# AuxilliaryLEDs.net
KiCad netlist of a schematic drawn in Altium Designer
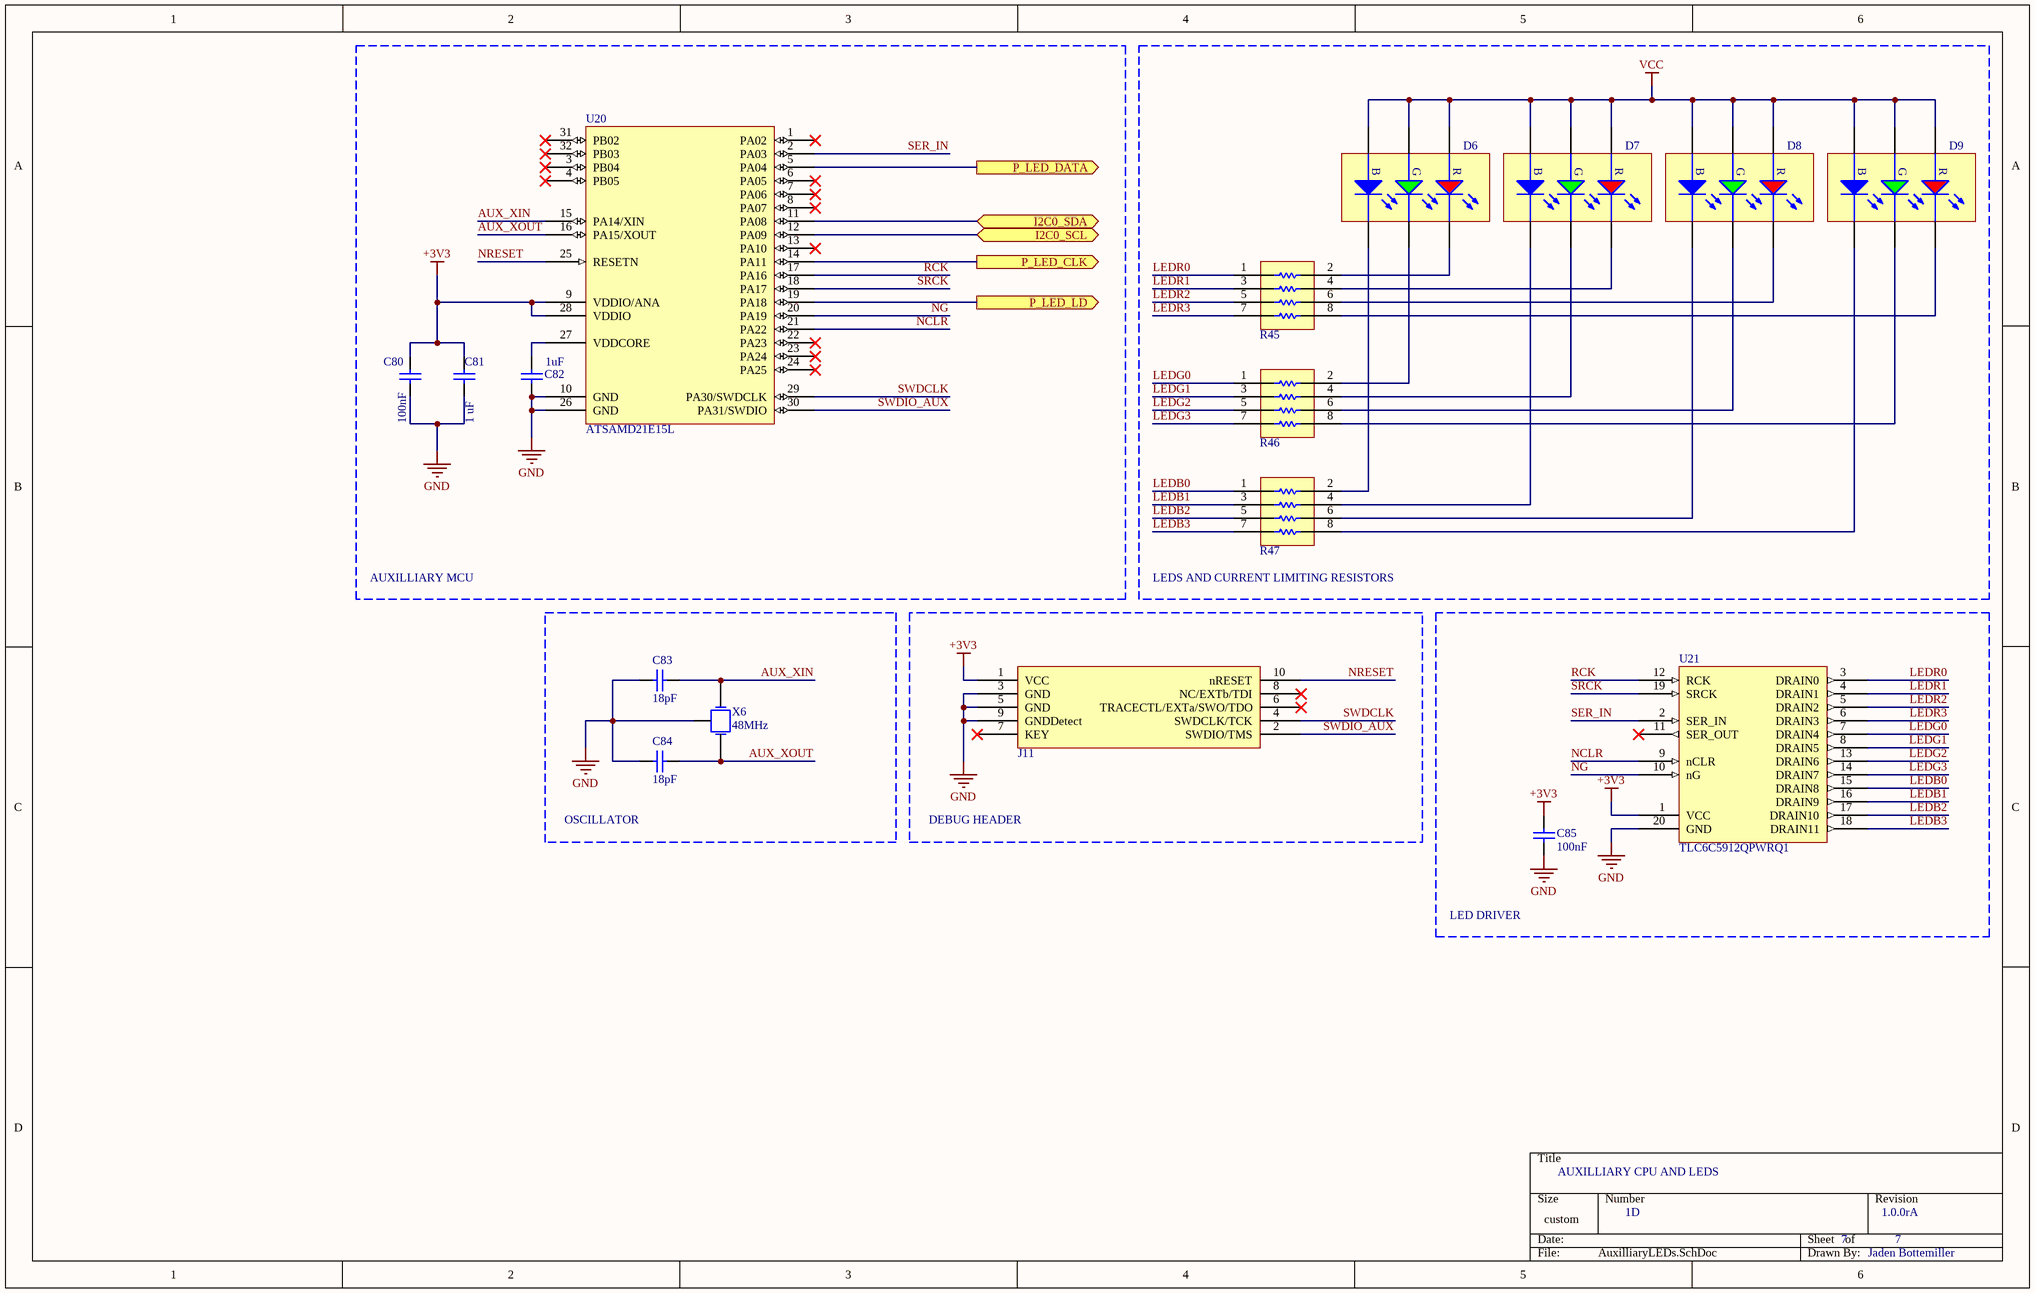
[diagram p0: AuxilliaryLEDs.SchDoc]

(export (version "E")
  (design (tool "Eeschema 10.0.6"))
  (components
    (comp (ref "C80")
      (value "100nF")
      (description "Standard Capacitor")
      (fields (field (name "Comment") "CAP"))
      (libsource (lib "NikoboticsLib") (part "CAP"))
    )
    (comp (ref "C81")
      (value "1 uF")
      (description "Standard Capacitor")
      (fields (field (name "Comment") "CAP"))
      (libsource (lib "NikoboticsLib") (part "CAP"))
    )
    (comp (ref "C82")
      (value "1uF")
      (description "Standard Capacitor")
      (fields (field (name "Comment") "CAP"))
      (libsource (lib "NikoboticsLib") (part "CAP"))
    )
    (comp (ref "C83")
      (value "18pF")
      (description "Standard Capacitor")
      (fields (field (name "Comment") "CAP"))
      (libsource (lib "NikoboticsLib") (part "CAP"))
    )
    (comp (ref "C84")
      (value "18pF")
      (description "Standard Capacitor")
      (fields (field (name "Comment") "CAP"))
      (libsource (lib "NikoboticsLib") (part "CAP"))
    )
    (comp (ref "C85")
      (value "100nF")
      (description "Standard Capacitor")
      (fields (field (name "Comment") "CAP"))
      (libsource (lib "NikoboticsLib") (part "CAP"))
    )
    (comp (ref "D6")
      (value "RGB LED")
      (description "3-Channel LED (RGB)")
      (libsource (lib "NikoboticsLib") (part "RGB_LED"))
    )
    (comp (ref "D7")
      (value "RGB LED")
      (description "3-Channel LED (RGB)")
      (libsource (lib "NikoboticsLib") (part "RGB_LED"))
    )
    (comp (ref "D8")
      (value "RGB LED")
      (description "3-Channel LED (RGB)")
      (libsource (lib "NikoboticsLib") (part "RGB_LED"))
    )
    (comp (ref "D9")
      (value "RGB LED")
      (description "3-Channel LED (RGB)")
      (libsource (lib "NikoboticsLib") (part "RGB_LED"))
    )
    (comp (ref "J11")
      (value "Debug Connector")
      (description "10-Pin Cortex-M Debug Connector")
      (libsource (lib "NikoboticsLib") (part "Cortex-M Debug"))
    )
    (comp (ref "R45")
      (value "RESNET")
      (description "Standard Resistor Network with 4 Resistors")
      (libsource (lib "NikoboticsLib") (part "RESNET4"))
    )
    (comp (ref "R46")
      (value "RESNET")
      (description "Standard Resistor Network with 4 Resistors")
      (libsource (lib "NikoboticsLib") (part "RESNET4"))
    )
    (comp (ref "R47")
      (value "RESNET")
      (description "Standard Resistor Network with 4 Resistors")
      (libsource (lib "NikoboticsLib") (part "RESNET4"))
    )
    (comp (ref "U20")
      (value "ATSAMD21E15L")
      (description "ARM® Cortex®-M0+ SAM D21E Microcontroller IC 32-Bit 48MHz 32KB (32K x 8) FLASH")
      (libsource (lib "NikoboticsLib") (part "ATSAMD21E15L"))
    )
    (comp (ref "U21")
      (value "TLC6C5912QPWRQ1")
      (description "LED Driver IC 12 Output Linear Shift Register 50mA")
      (libsource (lib "NikoboticsLib") (part "TLC6C5912QPWRQ1"))
    )
    (comp (ref "X6")
      (value "48MHz")
      (description "Standard Crystal Oscillator with a ground connection.")
      (fields (field (name "Comment") "Crystal Oscillator"))
      (libsource (lib "NikoboticsLib") (part "OSC_1GND"))
    )
  )
  (nets
    (net (code "1") (name "+3V3") (class "Default")
      (node (ref "C80") (pin "2") (pinfunction "2_2") (pintype "passive"))
      (node (ref "C81") (pin "2") (pinfunction "2_2") (pintype "passive"))
      (node (ref "C85") (pin "2") (pinfunction "2_2") (pintype "passive"))
      (node (ref "J11") (pin "1") (pinfunction "VCC_1") (pintype "power_in"))
      (node (ref "U20") (pin "28") (pinfunction "VDDIO_28") (pintype "power_in"))
      (node (ref "U20") (pin "9") (pinfunction "VDDIO/ANA_9") (pintype "power_in"))
      (node (ref "U21") (pin "1") (pinfunction "VCC_1") (pintype "power_in"))
    )
    (net (code "3") (name "/AUX_XIN") (class "Default")
      (node (ref "C83") (pin "1") (pinfunction "1_1") (pintype "passive"))
      (node (ref "U20") (pin "15") (pinfunction "PA14/XIN_15") (pintype "bidirectional"))
      (node (ref "X6") (pin "1") (pinfunction "X1_1") (pintype "passive"))
    )
    (net (code "4") (name "/AUX_XOUT") (class "Default")
      (node (ref "C84") (pin "1") (pinfunction "1_1") (pintype "passive"))
      (node (ref "U20") (pin "16") (pinfunction "PA15/XOUT_16") (pintype "bidirectional"))
      (node (ref "X6") (pin "2") (pinfunction "X2_2") (pintype "passive"))
    )
    (net (code "5") (name "/I2C0_SCL") (class "Default")
      (node (ref "U20") (pin "12") (pinfunction "PA09_12") (pintype "bidirectional"))
    )
    (net (code "6") (name "/I2C0_SDA") (class "Default")
      (node (ref "U20") (pin "11") (pinfunction "PA08_11") (pintype "bidirectional"))
    )
    (net (code "7") (name "/LEDB0") (class "Default")
      (node (ref "R47") (pin "1") (pinfunction "Pin_1") (pintype "passive"))
      (node (ref "U21") (pin "15") (pinfunction "DRAIN8_15") (pintype "output"))
    )
    (net (code "8") (name "/LEDB1") (class "Default")
      (node (ref "R47") (pin "3") (pinfunction "Pin_3") (pintype "passive"))
      (node (ref "U21") (pin "16") (pinfunction "DRAIN9_16") (pintype "output"))
    )
    (net (code "9") (name "/LEDB2") (class "Default")
      (node (ref "R47") (pin "5") (pinfunction "Pin_5") (pintype "passive"))
      (node (ref "U21") (pin "17") (pinfunction "DRAIN10_17") (pintype "output"))
    )
    (net (code "10") (name "/LEDB3") (class "Default")
      (node (ref "R47") (pin "7") (pinfunction "Pin_7") (pintype "passive"))
      (node (ref "U21") (pin "18") (pinfunction "DRAIN11_18") (pintype "output"))
    )
    (net (code "11") (name "/LEDG0") (class "Default")
      (node (ref "R46") (pin "1") (pinfunction "Pin_1") (pintype "passive"))
      (node (ref "U21") (pin "7") (pinfunction "DRAIN4_7") (pintype "output"))
    )
    (net (code "12") (name "/LEDG1") (class "Default")
      (node (ref "R46") (pin "3") (pinfunction "Pin_3") (pintype "passive"))
      (node (ref "U21") (pin "8") (pinfunction "DRAIN5_8") (pintype "output"))
    )
    (net (code "13") (name "/LEDG2") (class "Default")
      (node (ref "R46") (pin "5") (pinfunction "Pin_5") (pintype "passive"))
      (node (ref "U21") (pin "13") (pinfunction "DRAIN6_13") (pintype "output"))
    )
    (net (code "14") (name "/LEDG3") (class "Default")
      (node (ref "R46") (pin "7") (pinfunction "Pin_7") (pintype "passive"))
      (node (ref "U21") (pin "14") (pinfunction "DRAIN7_14") (pintype "output"))
    )
    (net (code "15") (name "/LEDR0") (class "Default")
      (node (ref "R45") (pin "1") (pinfunction "Pin_1") (pintype "passive"))
      (node (ref "U21") (pin "3") (pinfunction "DRAIN0_3") (pintype "output"))
    )
    (net (code "16") (name "/LEDR1") (class "Default")
      (node (ref "R45") (pin "3") (pinfunction "Pin_3") (pintype "passive"))
      (node (ref "U21") (pin "4") (pinfunction "DRAIN1_4") (pintype "output"))
    )
    (net (code "17") (name "/LEDR2") (class "Default")
      (node (ref "R45") (pin "5") (pinfunction "Pin_5") (pintype "passive"))
      (node (ref "U21") (pin "5") (pinfunction "DRAIN2_5") (pintype "output"))
    )
    (net (code "18") (name "/LEDR3") (class "Default")
      (node (ref "R45") (pin "7") (pinfunction "Pin_7") (pintype "passive"))
      (node (ref "U21") (pin "6") (pinfunction "DRAIN3_6") (pintype "output"))
    )
    (net (code "19") (name "/NCLR") (class "Default")
      (node (ref "U20") (pin "21") (pinfunction "PA22_21") (pintype "bidirectional"))
      (node (ref "U21") (pin "9") (pinfunction "nCLR_9") (pintype "input"))
    )
    (net (code "20") (name "/NG") (class "Default")
      (node (ref "U20") (pin "20") (pinfunction "PA19_20") (pintype "bidirectional"))
      (node (ref "U21") (pin "10") (pinfunction "nG_10") (pintype "input"))
    )
    (net (code "21") (name "/NRESET") (class "Default")
      (node (ref "J11") (pin "10") (pinfunction "nRESET_10") (pintype "passive"))
      (node (ref "U20") (pin "25") (pinfunction "RESETN_25") (pintype "input"))
    )
    (net (code "22") (name "/P_LED_CLK") (class "Default")
      (node (ref "U20") (pin "14") (pinfunction "PA11_14") (pintype "bidirectional"))
    )
    (net (code "23") (name "/P_LED_DATA") (class "Default")
      (node (ref "U20") (pin "5") (pinfunction "PA04_5") (pintype "bidirectional"))
    )
    (net (code "24") (name "/P_LED_LD") (class "Default")
      (node (ref "U20") (pin "19") (pinfunction "PA18_19") (pintype "bidirectional"))
    )
    (net (code "25") (name "/RCK") (class "Default")
      (node (ref "U20") (pin "17") (pinfunction "PA16_17") (pintype "bidirectional"))
      (node (ref "U21") (pin "12") (pinfunction "RCK_12") (pintype "input"))
    )
    (net (code "26") (name "/SER_IN") (class "Default")
      (node (ref "U20") (pin "2") (pinfunction "PA03_2") (pintype "bidirectional"))
      (node (ref "U21") (pin "2") (pinfunction "SER_IN_2") (pintype "input"))
    )
    (net (code "27") (name "/SRCK") (class "Default")
      (node (ref "U20") (pin "18") (pinfunction "PA17_18") (pintype "bidirectional"))
      (node (ref "U21") (pin "19") (pinfunction "SRCK_19") (pintype "input"))
    )
    (net (code "28") (name "/SWDCLK") (class "Default")
      (node (ref "J11") (pin "4") (pinfunction "SWDCLK/TCK_4") (pintype "passive"))
      (node (ref "U20") (pin "29") (pinfunction "PA30/SWDCLK_29") (pintype "bidirectional"))
    )
    (net (code "29") (name "/SWDIO_AUX") (class "Default")
      (node (ref "J11") (pin "2") (pinfunction "SWDIO/TMS_2") (pintype "passive"))
      (node (ref "U20") (pin "30") (pinfunction "PA31/SWDIO_30") (pintype "bidirectional"))
    )
    (net (code "30") (name "GND") (class "Default")
      (node (ref "C80") (pin "1") (pinfunction "1_1") (pintype "passive"))
      (node (ref "C81") (pin "1") (pinfunction "1_1") (pintype "passive"))
      (node (ref "C82") (pin "1") (pinfunction "1_1") (pintype "passive"))
      (node (ref "C83") (pin "2") (pinfunction "2_2") (pintype "passive"))
      (node (ref "C84") (pin "2") (pinfunction "2_2") (pintype "passive"))
      (node (ref "C85") (pin "1") (pinfunction "1_1") (pintype "passive"))
      (node (ref "J11") (pin "3") (pinfunction "GND_3") (pintype "power_in"))
      (node (ref "J11") (pin "5") (pinfunction "GND_5") (pintype "power_in"))
      (node (ref "J11") (pin "9") (pinfunction "GNDDetect_9") (pintype "power_in"))
      (node (ref "U20") (pin "10") (pinfunction "GND_10") (pintype "power_in"))
      (node (ref "U20") (pin "26") (pinfunction "GND_26") (pintype "power_in"))
      (node (ref "U21") (pin "20") (pinfunction "GND_20") (pintype "power_in"))
      (node (ref "X6") (pin "3") (pinfunction "GND_3") (pintype "passive"))
    )
    (net (code "31") (name "Net-(D6-BC)") (class "Default")
      (node (ref "D6") (pin "1") (pinfunction "BC_1") (pintype "passive"))
      (node (ref "R47") (pin "2") (pinfunction "Pin_2") (pintype "passive"))
    )
    (net (code "32") (name "Net-(D6-GC)") (class "Default")
      (node (ref "D6") (pin "2") (pinfunction "GC_2") (pintype "passive"))
      (node (ref "R46") (pin "2") (pinfunction "Pin_2") (pintype "passive"))
    )
    (net (code "33") (name "Net-(D6-RC)") (class "Default")
      (node (ref "D6") (pin "3") (pinfunction "RC_3") (pintype "passive"))
      (node (ref "R45") (pin "2") (pinfunction "Pin_2") (pintype "passive"))
    )
    (net (code "34") (name "Net-(D7-BC)") (class "Default")
      (node (ref "D7") (pin "1") (pinfunction "BC_1") (pintype "passive"))
      (node (ref "R47") (pin "4") (pinfunction "Pin_4") (pintype "passive"))
    )
    (net (code "35") (name "Net-(D7-GC)") (class "Default")
      (node (ref "D7") (pin "2") (pinfunction "GC_2") (pintype "passive"))
      (node (ref "R46") (pin "4") (pinfunction "Pin_4") (pintype "passive"))
    )
    (net (code "36") (name "Net-(D7-RC)") (class "Default")
      (node (ref "D7") (pin "3") (pinfunction "RC_3") (pintype "passive"))
      (node (ref "R45") (pin "4") (pinfunction "Pin_4") (pintype "passive"))
    )
    (net (code "37") (name "Net-(D8-BC)") (class "Default")
      (node (ref "D8") (pin "1") (pinfunction "BC_1") (pintype "passive"))
      (node (ref "R47") (pin "6") (pinfunction "Pin_6") (pintype "passive"))
    )
    (net (code "38") (name "Net-(D8-GC)") (class "Default")
      (node (ref "D8") (pin "2") (pinfunction "GC_2") (pintype "passive"))
      (node (ref "R46") (pin "6") (pinfunction "Pin_6") (pintype "passive"))
    )
    (net (code "39") (name "Net-(D8-RC)") (class "Default")
      (node (ref "D8") (pin "3") (pinfunction "RC_3") (pintype "passive"))
      (node (ref "R45") (pin "6") (pinfunction "Pin_6") (pintype "passive"))
    )
    (net (code "40") (name "Net-(D9-BC)") (class "Default")
      (node (ref "D9") (pin "1") (pinfunction "BC_1") (pintype "passive"))
      (node (ref "R47") (pin "8") (pinfunction "Pin_8") (pintype "passive"))
    )
    (net (code "41") (name "Net-(D9-GC)") (class "Default")
      (node (ref "D9") (pin "2") (pinfunction "GC_2") (pintype "passive"))
      (node (ref "R46") (pin "8") (pinfunction "Pin_8") (pintype "passive"))
    )
    (net (code "42") (name "Net-(D9-RC)") (class "Default")
      (node (ref "D9") (pin "3") (pinfunction "RC_3") (pintype "passive"))
      (node (ref "R45") (pin "8") (pinfunction "Pin_8") (pintype "passive"))
    )
    (net (code "43") (name "Net-(U20-VDDCORE)") (class "Default")
      (node (ref "C82") (pin "2") (pinfunction "2_2") (pintype "passive"))
      (node (ref "U20") (pin "27") (pinfunction "VDDCORE_27") (pintype "power_in"))
    )
    (net (code "44") (name "VCC") (class "Default")
      (node (ref "D6") (pin "4") (pinfunction "RA_4") (pintype "passive"))
      (node (ref "D6") (pin "5") (pinfunction "GA_5") (pintype "passive"))
      (node (ref "D6") (pin "6") (pinfunction "BA_6") (pintype "passive"))
      (node (ref "D7") (pin "4") (pinfunction "RA_4") (pintype "passive"))
      (node (ref "D7") (pin "5") (pinfunction "GA_5") (pintype "passive"))
      (node (ref "D7") (pin "6") (pinfunction "BA_6") (pintype "passive"))
      (node (ref "D8") (pin "4") (pinfunction "RA_4") (pintype "passive"))
      (node (ref "D8") (pin "5") (pinfunction "GA_5") (pintype "passive"))
      (node (ref "D8") (pin "6") (pinfunction "BA_6") (pintype "passive"))
      (node (ref "D9") (pin "4") (pinfunction "RA_4") (pintype "passive"))
      (node (ref "D9") (pin "5") (pinfunction "GA_5") (pintype "passive"))
      (node (ref "D9") (pin "6") (pinfunction "BA_6") (pintype "passive"))
    )
    (net (code "45") (name "unconnected-(J11-KEY-Pad7)") (class "Default")
      (node (ref "J11") (pin "7") (pinfunction "KEY_7") (pintype "passive+no_connect"))
    )
    (net (code "46") (name "unconnected-(J11-NC{slash}EXTb{slash}TDI-Pad8)") (class "Default")
      (node (ref "J11") (pin "8") (pinfunction "NC/EXTb/TDI_8") (pintype "passive+no_connect"))
    )
    (net (code "47") (name "unconnected-(J11-TRACECTL{slash}EXTa{slash}SWO{slash}TDO-Pad6)") (class "Default")
      (node (ref "J11") (pin "6") (pinfunction "TRACECTL/EXTa/SWO/TDO_6") (pintype "passive+no_connect"))
    )
    (net (code "48") (name "unconnected-(U20-PA02-Pad1)") (class "Default")
      (node (ref "U20") (pin "1") (pinfunction "PA02_1") (pintype "bidirectional+no_connect"))
    )
    (net (code "49") (name "unconnected-(U20-PA05-Pad6)") (class "Default")
      (node (ref "U20") (pin "6") (pinfunction "PA05_6") (pintype "bidirectional+no_connect"))
    )
    (net (code "50") (name "unconnected-(U20-PA06-Pad7)") (class "Default")
      (node (ref "U20") (pin "7") (pinfunction "PA06_7") (pintype "bidirectional+no_connect"))
    )
    (net (code "51") (name "unconnected-(U20-PA07-Pad8)") (class "Default")
      (node (ref "U20") (pin "8") (pinfunction "PA07_8") (pintype "bidirectional+no_connect"))
    )
    (net (code "52") (name "unconnected-(U20-PA10-Pad13)") (class "Default")
      (node (ref "U20") (pin "13") (pinfunction "PA10_13") (pintype "bidirectional+no_connect"))
    )
    (net (code "53") (name "unconnected-(U20-PA23-Pad22)") (class "Default")
      (node (ref "U20") (pin "22") (pinfunction "PA23_22") (pintype "bidirectional+no_connect"))
    )
    (net (code "54") (name "unconnected-(U20-PA24-Pad23)") (class "Default")
      (node (ref "U20") (pin "23") (pinfunction "PA24_23") (pintype "bidirectional+no_connect"))
    )
    (net (code "55") (name "unconnected-(U20-PA25-Pad24)") (class "Default")
      (node (ref "U20") (pin "24") (pinfunction "PA25_24") (pintype "bidirectional+no_connect"))
    )
    (net (code "56") (name "unconnected-(U20-PB02-Pad31)") (class "Default")
      (node (ref "U20") (pin "31") (pinfunction "PB02_31") (pintype "bidirectional+no_connect"))
    )
    (net (code "57") (name "unconnected-(U20-PB03-Pad32)") (class "Default")
      (node (ref "U20") (pin "32") (pinfunction "PB03_32") (pintype "bidirectional+no_connect"))
    )
    (net (code "58") (name "unconnected-(U20-PB04-Pad3)") (class "Default")
      (node (ref "U20") (pin "3") (pinfunction "PB04_3") (pintype "bidirectional+no_connect"))
    )
    (net (code "59") (name "unconnected-(U20-PB05-Pad4)") (class "Default")
      (node (ref "U20") (pin "4") (pinfunction "PB05_4") (pintype "bidirectional+no_connect"))
    )
    (net (code "60") (name "unconnected-(U21-SER_OUT-Pad11)") (class "Default")
      (node (ref "U21") (pin "11") (pinfunction "SER_OUT_11") (pintype "output+no_connect"))
    )
  )
)
